# LoRa_Gateway_ESP32_-_Final.net
KiCad netlist of a schematic drawn in EAGLE
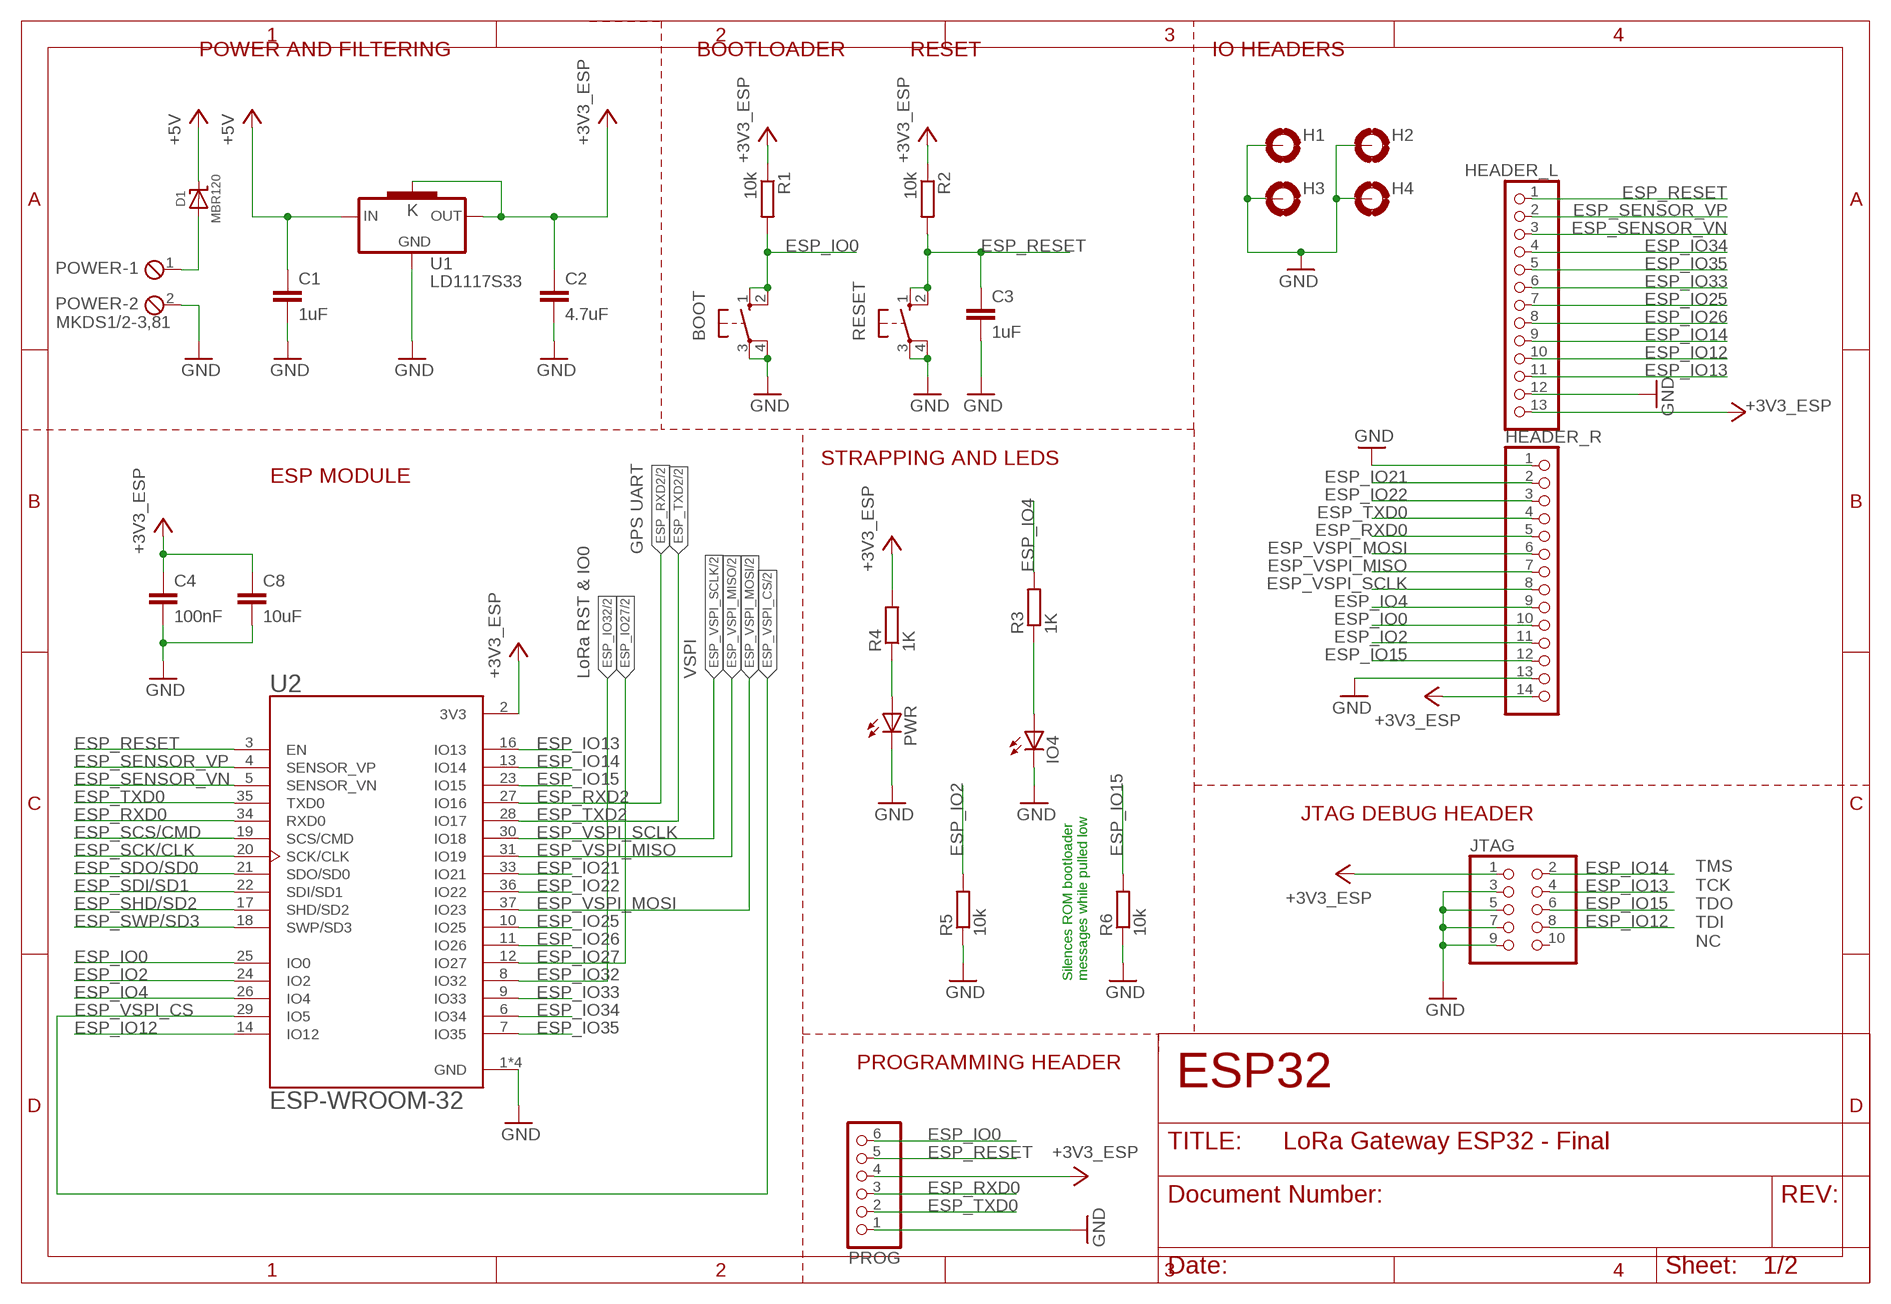
[diagram p0: schematic, sheet 1]
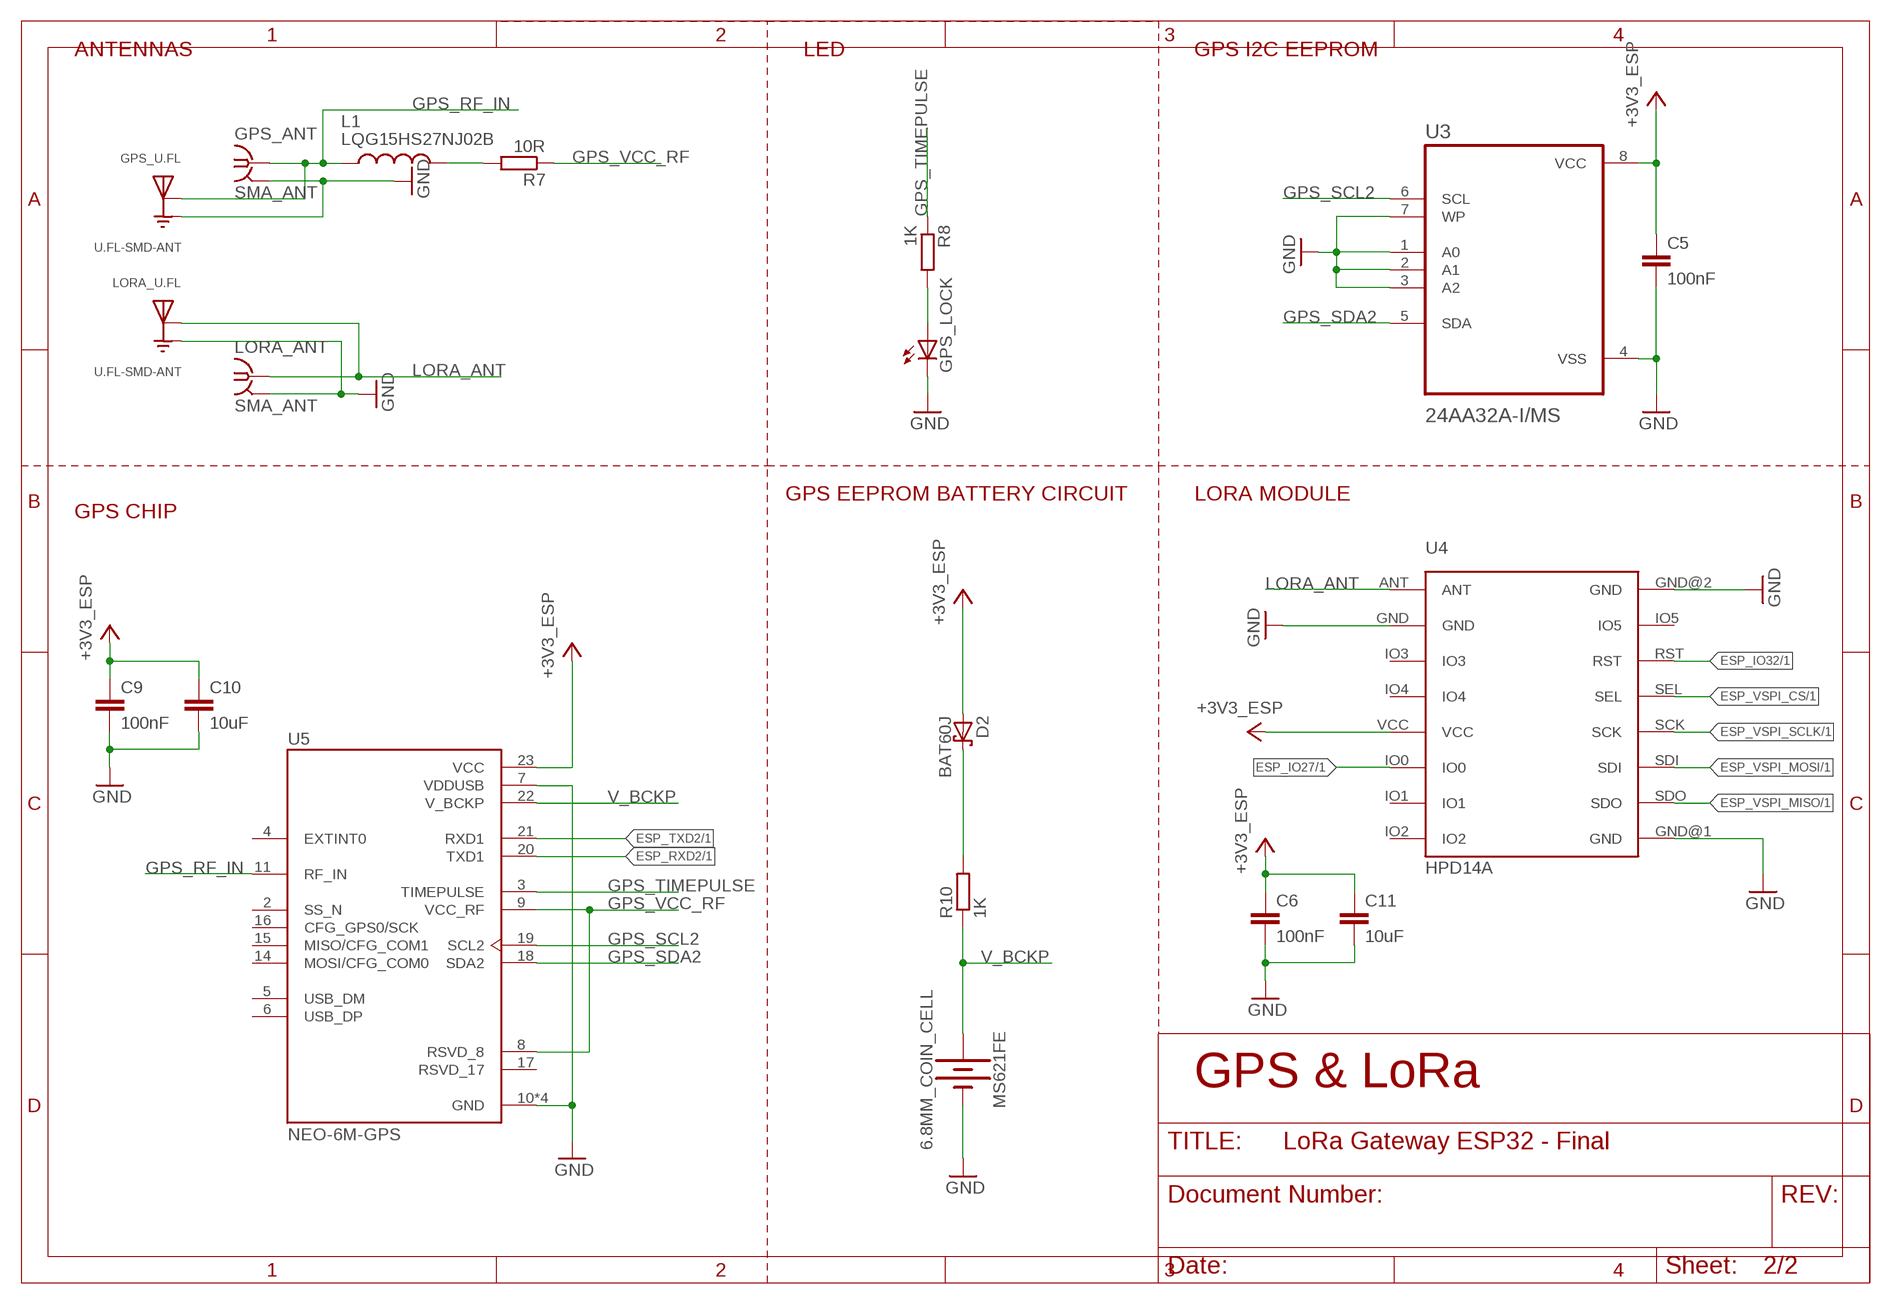
[diagram p1: schematic, sheet 2]

(export (version "E")
  (design (tool "Eeschema 10.0.6"))
  (components
    (comp (ref "C5")
      (value "100nF")
      (footprint "eagle-import:C0805K")
      (libsource (lib "eagle-import") (part "C-EUC0805K"))
    )
    (comp (ref "C6")
      (value "100nF")
      (footprint "eagle-import:C0805K")
      (libsource (lib "eagle-import") (part "C-EUC0805K"))
    )
    (comp (ref "C9")
      (value "100nF")
      (footprint "eagle-import:C0805K")
      (libsource (lib "eagle-import") (part "C-EUC0805K"))
    )
    (comp (ref "C10")
      (value "10uF")
      (footprint "eagle-import:C0805K")
      (libsource (lib "eagle-import") (part "C-EUC0805K"))
    )
    (comp (ref "C11")
      (value "10uF")
      (footprint "eagle-import:C0805K")
      (libsource (lib "eagle-import") (part "C-EUC0805K"))
    )
    (comp (ref "D2")
      (value "BAT60J")
      (footprint "eagle-import:SOD323_ST")
      (libsource (lib "eagle-import") (part "BAT60J"))
    )
    (comp (ref "GPS_ANT")
      (value "SMA_ANT")
      (footprint "eagle-import:BU-SMA-H")
      (libsource (lib "eagle-import") (part "SMA_ANT"))
    )
    (comp (ref "GPS_LOCK")
      (value "LEDCHIP-LED0805")
      (footprint "eagle-import:CHIP-LED0805")
      (libsource (lib "eagle-import") (part "LEDCHIP-LED0805"))
    )
    (comp (ref "GPS_U.FL")
      (value "U.FL-SMD-ANT")
      (footprint "eagle-import:HRS_U.FL-R-SMT-1(10)")
      (fields (field (name "MF") "Hirose") (field (name "MP") "U.FL-R-SMT-1(10)"))
      (libsource (lib "eagle-import") (part "U.FL-SMD-ANT"))
    )
    (comp (ref "L1")
      (value "LQG15HS27NJ02B")
      (footprint "eagle-import:INDC1005X55N")
      (fields (field (name "MF") "Murata"))
      (libsource (lib "eagle-import") (part "LQG15HS27NJ02B"))
    )
    (comp (ref "LORA_ANT")
      (value "SMA_ANT")
      (footprint "eagle-import:BU-SMA-H")
      (libsource (lib "eagle-import") (part "SMA_ANT"))
    )
    (comp (ref "LORA_U.FL")
      (value "U.FL-SMD-ANT")
      (footprint "eagle-import:HRS_U.FL-R-SMT-1(10)")
      (fields (field (name "MF") "Hirose") (field (name "MP") "U.FL-R-SMT-1(10)"))
      (libsource (lib "eagle-import") (part "U.FL-SMD-ANT"))
    )
    (comp (ref "MS621FE")
      (value "6.8MM_COIN_CELL")
      (footprint "eagle-import:BATTCON-6.8MM")
      (libsource (lib "eagle-import") (part "BATTERY-6.8MM_SMD"))
    )
    (comp (ref "R7")
      (value "10R")
      (footprint "eagle-import:R0805")
      (libsource (lib "eagle-import") (part "R-EU_R0805"))
    )
    (comp (ref "R8")
      (value "1K")
      (footprint "eagle-import:R0805")
      (libsource (lib "eagle-import") (part "R-EU_R0805"))
    )
    (comp (ref "R10")
      (value "1K")
      (footprint "eagle-import:R0805")
      (libsource (lib "eagle-import") (part "R-EU_R0805"))
    )
    (comp (ref "U3")
      (value "24AA32A-I/MS")
      (footprint "eagle-import:SOP65P490X110-8N")
      (fields (field (name "MF") "Microchip"))
      (libsource (lib "eagle-import") (part "24AA32A-I/MS"))
    )
    (comp (ref "U4")
      (value "HPD14A")
      (footprint "eagle-import:HPD14A")
      (libsource (lib "eagle-import") (part "HPD14A"))
    )
    (comp (ref "U5")
      (value "NEO-6M-GPS")
      (footprint "eagle-import:XCVR_NEO-6M-GPS")
      (fields (field (name "MF") "u-blox"))
      (libsource (lib "eagle-import") (part "NEO-6M-GPS"))
    )
    (comp (ref "BOOT")
      (value "10-XX")
      (footprint "eagle-import:B3F-10XX")
      (fields (field (name "MPN") "B3F-1000"))
      (libsource (lib "eagle-import") (part "10-XX"))
    )
    (comp (ref "C1")
      (value "1uF")
      (footprint "eagle-import:C0805K")
      (libsource (lib "eagle-import") (part "C-EUC0805K"))
    )
    (comp (ref "C2")
      (value "4.7uF")
      (footprint "eagle-import:C0805K")
      (libsource (lib "eagle-import") (part "C-EUC0805K"))
    )
    (comp (ref "C3")
      (value "1uF")
      (footprint "eagle-import:C0805K")
      (libsource (lib "eagle-import") (part "C-EUC0805K"))
    )
    (comp (ref "C4")
      (value "100nF")
      (footprint "eagle-import:C0805K")
      (libsource (lib "eagle-import") (part "C-EUC0805K"))
    )
    (comp (ref "C8")
      (value "10uF")
      (footprint "eagle-import:C0805K")
      (libsource (lib "eagle-import") (part "C-EUC0805K"))
    )
    (comp (ref "D1")
      (value "MBR120")
      (footprint "eagle-import:SOD-123")
      (libsource (lib "eagle-import") (part "DIODE-SCHOTTKYSOD-123"))
    )
    (comp (ref "H1")
      (value "MOUNT-PAD-ROUND3.2")
      (footprint "eagle-import:3,2-PAD")
      (libsource (lib "eagle-import") (part "MOUNT-PAD-ROUND3.2"))
    )
    (comp (ref "H2")
      (value "MOUNT-PAD-ROUND3.2")
      (footprint "eagle-import:3,2-PAD")
      (libsource (lib "eagle-import") (part "MOUNT-PAD-ROUND3.2"))
    )
    (comp (ref "H3")
      (value "MOUNT-PAD-ROUND3.2")
      (footprint "eagle-import:3,2-PAD")
      (libsource (lib "eagle-import") (part "MOUNT-PAD-ROUND3.2"))
    )
    (comp (ref "H4")
      (value "MOUNT-PAD-ROUND3.2")
      (footprint "eagle-import:3,2-PAD")
      (libsource (lib "eagle-import") (part "MOUNT-PAD-ROUND3.2"))
    )
    (comp (ref "HEADER_L")
      (value "PINHD-1X13")
      (footprint "eagle-import:1X13")
      (libsource (lib "eagle-import") (part "PINHD-1X13"))
    )
    (comp (ref "HEADER_R")
      (value "PINHD-1X14")
      (footprint "eagle-import:1X14")
      (libsource (lib "eagle-import") (part "PINHD-1X14"))
    )
    (comp (ref "IO4")
      (value "LEDCHIP-LED0805")
      (footprint "eagle-import:CHIP-LED0805")
      (libsource (lib "eagle-import") (part "LEDCHIP-LED0805"))
    )
    (comp (ref "JTAG")
      (value "PINHD-2X5")
      (footprint "eagle-import:2X05")
      (libsource (lib "eagle-import") (part "PINHD-2X5"))
    )
    (comp (ref "POWER")
      (value "MKDS1/2-3,81")
      (footprint "eagle-import:2POL381")
      (libsource (lib "eagle-import") (part "MKDS1/2-3,81"))
    )
    (comp (ref "PROG")
      (value "PINHD-1X6")
      (footprint "eagle-import:1X06")
      (libsource (lib "eagle-import") (part "PINHD-1X6"))
    )
    (comp (ref "PWR")
      (value "LEDCHIP-LED0805")
      (footprint "eagle-import:CHIP-LED0805")
      (libsource (lib "eagle-import") (part "LEDCHIP-LED0805"))
    )
    (comp (ref "R1")
      (value "10k")
      (footprint "eagle-import:R0805")
      (libsource (lib "eagle-import") (part "R-EU_R0805"))
    )
    (comp (ref "R2")
      (value "10k")
      (footprint "eagle-import:R0805")
      (libsource (lib "eagle-import") (part "R-EU_R0805"))
    )
    (comp (ref "R3")
      (value "1K")
      (footprint "eagle-import:R0805")
      (libsource (lib "eagle-import") (part "R-EU_R0805"))
    )
    (comp (ref "R4")
      (value "1K")
      (footprint "eagle-import:R0805")
      (libsource (lib "eagle-import") (part "R-EU_R0805"))
    )
    (comp (ref "R5")
      (value "10k")
      (footprint "eagle-import:R0805")
      (libsource (lib "eagle-import") (part "R-EU_R0805"))
    )
    (comp (ref "R6")
      (value "10k")
      (footprint "eagle-import:R0805")
      (libsource (lib "eagle-import") (part "R-EU_R0805"))
    )
    (comp (ref "RESET")
      (value "10-XX")
      (footprint "eagle-import:B3F-10XX")
      (fields (field (name "MPN") "B3F-1000"))
      (libsource (lib "eagle-import") (part "10-XX"))
    )
    (comp (ref "U1")
      (value "LD1117S33")
      (footprint "eagle-import:SOT223")
      (fields (field (name "MF") "STMicroelectronics"))
      (libsource (lib "eagle-import") (part "LD1117S33"))
    )
    (comp (ref "U2")
      (value "ESP-WROOM-32")
      (footprint "eagle-import:MODULE_ESP-WROOM-32")
      (fields (field (name "MF") "Olimex LTD"))
      (libsource (lib "eagle-import") (part "ESP-WROOM-32"))
    )
  )
  (nets
    (net (code "1") (name "+3V3_ESP") (class "Default")
      (node (ref "C10") (pin "1") (pinfunction "1_1") (pintype "passive"))
      (node (ref "C11") (pin "1") (pinfunction "1_1") (pintype "passive"))
      (node (ref "C2") (pin "1") (pinfunction "1_1") (pintype "passive"))
      (node (ref "C4") (pin "1") (pinfunction "1_1") (pintype "passive"))
      (node (ref "C5") (pin "1") (pinfunction "1_1") (pintype "passive"))
      (node (ref "C6") (pin "1") (pinfunction "1_1") (pintype "passive"))
      (node (ref "C8") (pin "1") (pinfunction "1_1") (pintype "passive"))
      (node (ref "C9") (pin "1") (pinfunction "1_1") (pintype "passive"))
      (node (ref "D2") (pin "A") (pinfunction "A_A") (pintype "passive"))
      (node (ref "HEADER_L") (pin "13") (pinfunction "13_13") (pintype "passive"))
      (node (ref "HEADER_R") (pin "14") (pinfunction "14_14") (pintype "passive"))
      (node (ref "JTAG") (pin "1") (pinfunction "1_1") (pintype "passive"))
      (node (ref "PROG") (pin "4") (pinfunction "4_4") (pintype "passive"))
      (node (ref "R1") (pin "1") (pinfunction "1_1") (pintype "passive"))
      (node (ref "R2") (pin "1") (pinfunction "1_1") (pintype "passive"))
      (node (ref "R4") (pin "2") (pinfunction "2_2") (pintype "passive"))
      (node (ref "U1") (pin "2") (pinfunction "OUT_2") (pintype "passive"))
      (node (ref "U1") (pin "4") (pinfunction "K_4") (pintype "passive"))
      (node (ref "U2") (pin "2") (pinfunction "3V3_2") (pintype "power_in"))
      (node (ref "U3") (pin "8") (pinfunction "VCC_8") (pintype "power_in"))
      (node (ref "U4") (pin "VCC") (pinfunction "VCC_VCC") (pintype "bidirectional"))
      (node (ref "U5") (pin "23") (pinfunction "VCC_23") (pintype "power_in"))
    )
    (net (code "2") (name "+5V") (class "Default")
      (node (ref "C1") (pin "1") (pinfunction "1_1") (pintype "passive"))
      (node (ref "D1") (pin "C") (pinfunction "C_C") (pintype "passive"))
      (node (ref "U1") (pin "3") (pinfunction "IN_3") (pintype "input"))
    )
    (net (code "3") (name "ESP_IO0") (class "Default")
      (node (ref "BOOT") (pin "1") (pinfunction "S_1") (pintype "passive"))
      (node (ref "BOOT") (pin "2") (pinfunction "S1_2") (pintype "passive"))
      (node (ref "HEADER_R") (pin "10") (pinfunction "10_10") (pintype "passive"))
      (node (ref "PROG") (pin "6") (pinfunction "6_6") (pintype "passive"))
      (node (ref "R1") (pin "2") (pinfunction "2_2") (pintype "passive"))
      (node (ref "U2") (pin "25") (pinfunction "IO0_25") (pintype "bidirectional"))
    )
    (net (code "4") (name "ESP_IO2") (class "Default")
      (node (ref "HEADER_R") (pin "11") (pinfunction "11_11") (pintype "passive"))
      (node (ref "R5") (pin "2") (pinfunction "2_2") (pintype "passive"))
      (node (ref "U2") (pin "24") (pinfunction "IO2_24") (pintype "bidirectional"))
    )
    (net (code "5") (name "ESP_IO4") (class "Default")
      (node (ref "HEADER_R") (pin "9") (pinfunction "9_9") (pintype "passive"))
      (node (ref "R3") (pin "2") (pinfunction "2_2") (pintype "passive"))
      (node (ref "U2") (pin "26") (pinfunction "IO4_26") (pintype "bidirectional"))
    )
    (net (code "6") (name "ESP_IO12") (class "Default")
      (node (ref "HEADER_L") (pin "10") (pinfunction "10_10") (pintype "passive"))
      (node (ref "JTAG") (pin "8") (pinfunction "8_8") (pintype "passive"))
      (node (ref "U2") (pin "14") (pinfunction "IO12_14") (pintype "bidirectional"))
    )
    (net (code "7") (name "ESP_IO13") (class "Default")
      (node (ref "HEADER_L") (pin "11") (pinfunction "11_11") (pintype "passive"))
      (node (ref "JTAG") (pin "4") (pinfunction "4_4") (pintype "passive"))
      (node (ref "U2") (pin "16") (pinfunction "IO13_16") (pintype "bidirectional"))
    )
    (net (code "8") (name "ESP_IO14") (class "Default")
      (node (ref "HEADER_L") (pin "9") (pinfunction "9_9") (pintype "passive"))
      (node (ref "JTAG") (pin "2") (pinfunction "2_2") (pintype "passive"))
      (node (ref "U2") (pin "13") (pinfunction "IO14_13") (pintype "bidirectional"))
    )
    (net (code "9") (name "ESP_IO15") (class "Default")
      (node (ref "HEADER_R") (pin "12") (pinfunction "12_12") (pintype "passive"))
      (node (ref "JTAG") (pin "6") (pinfunction "6_6") (pintype "passive"))
      (node (ref "R6") (pin "2") (pinfunction "2_2") (pintype "passive"))
      (node (ref "U2") (pin "23") (pinfunction "IO15_23") (pintype "bidirectional"))
    )
    (net (code "10") (name "ESP_IO21") (class "Default")
      (node (ref "HEADER_R") (pin "2") (pinfunction "2_2") (pintype "passive"))
      (node (ref "U2") (pin "33") (pinfunction "IO21_33") (pintype "bidirectional"))
    )
    (net (code "11") (name "ESP_IO22") (class "Default")
      (node (ref "HEADER_R") (pin "3") (pinfunction "3_3") (pintype "passive"))
      (node (ref "U2") (pin "36") (pinfunction "IO22_36") (pintype "bidirectional"))
    )
    (net (code "12") (name "ESP_IO25") (class "Default")
      (node (ref "HEADER_L") (pin "7") (pinfunction "7_7") (pintype "passive"))
      (node (ref "U2") (pin "10") (pinfunction "IO25_10") (pintype "bidirectional"))
    )
    (net (code "13") (name "ESP_IO26") (class "Default")
      (node (ref "HEADER_L") (pin "8") (pinfunction "8_8") (pintype "passive"))
      (node (ref "U2") (pin "11") (pinfunction "IO26_11") (pintype "bidirectional"))
    )
    (net (code "14") (name "ESP_IO27") (class "Default")
      (node (ref "U2") (pin "12") (pinfunction "IO27_12") (pintype "bidirectional"))
      (node (ref "U4") (pin "IO0") (pinfunction "IO0_IO0") (pintype "bidirectional"))
    )
    (net (code "15") (name "ESP_IO32") (class "Default")
      (node (ref "U2") (pin "8") (pinfunction "IO32_8") (pintype "bidirectional"))
      (node (ref "U4") (pin "RST") (pinfunction "RST_RST") (pintype "bidirectional"))
    )
    (net (code "16") (name "ESP_IO33") (class "Default")
      (node (ref "HEADER_L") (pin "6") (pinfunction "6_6") (pintype "passive"))
      (node (ref "U2") (pin "9") (pinfunction "IO33_9") (pintype "bidirectional"))
    )
    (net (code "17") (name "ESP_IO34") (class "Default")
      (node (ref "HEADER_L") (pin "4") (pinfunction "4_4") (pintype "passive"))
      (node (ref "U2") (pin "6") (pinfunction "IO34_6") (pintype "bidirectional"))
    )
    (net (code "18") (name "ESP_IO35") (class "Default")
      (node (ref "HEADER_L") (pin "5") (pinfunction "5_5") (pintype "passive"))
      (node (ref "U2") (pin "7") (pinfunction "IO35_7") (pintype "bidirectional"))
    )
    (net (code "19") (name "ESP_RESET") (class "Default")
      (node (ref "C3") (pin "1") (pinfunction "1_1") (pintype "passive"))
      (node (ref "HEADER_L") (pin "1") (pinfunction "1_1") (pintype "passive"))
      (node (ref "PROG") (pin "5") (pinfunction "5_5") (pintype "passive"))
      (node (ref "R2") (pin "2") (pinfunction "2_2") (pintype "passive"))
      (node (ref "RESET") (pin "1") (pinfunction "S_1") (pintype "passive"))
      (node (ref "RESET") (pin "2") (pinfunction "S1_2") (pintype "passive"))
      (node (ref "U2") (pin "3") (pinfunction "EN_3") (pintype "input"))
    )
    (net (code "20") (name "ESP_RXD0") (class "Default")
      (node (ref "HEADER_R") (pin "5") (pinfunction "5_5") (pintype "passive"))
      (node (ref "PROG") (pin "3") (pinfunction "3_3") (pintype "passive"))
      (node (ref "U2") (pin "34") (pinfunction "RXD0_34") (pintype "bidirectional"))
    )
    (net (code "21") (name "ESP_RXD2") (class "Default")
      (node (ref "U2") (pin "27") (pinfunction "IO16_27") (pintype "bidirectional"))
      (node (ref "U5") (pin "20") (pinfunction "TXD1_20") (pintype "output"))
    )
    (net (code "22") (name "ESP_SCK{slash}CLK") (class "Default")
      (node (ref "U2") (pin "20") (pinfunction "SCK/CLK_20") (pintype "bidirectional"))
    )
    (net (code "23") (name "ESP_SCS{slash}CMD") (class "Default")
      (node (ref "U2") (pin "19") (pinfunction "SCS/CMD_19") (pintype "bidirectional"))
    )
    (net (code "24") (name "ESP_SDI{slash}SD1") (class "Default")
      (node (ref "U2") (pin "22") (pinfunction "SDI/SD1_22") (pintype "bidirectional"))
    )
    (net (code "25") (name "ESP_SDO{slash}SD0") (class "Default")
      (node (ref "U2") (pin "21") (pinfunction "SDO/SD0_21") (pintype "bidirectional"))
    )
    (net (code "26") (name "ESP_SENSOR_VN") (class "Default")
      (node (ref "HEADER_L") (pin "3") (pinfunction "3_3") (pintype "passive"))
      (node (ref "U2") (pin "5") (pinfunction "SENSOR_VN_5") (pintype "input"))
    )
    (net (code "27") (name "ESP_SENSOR_VP") (class "Default")
      (node (ref "HEADER_L") (pin "2") (pinfunction "2_2") (pintype "passive"))
      (node (ref "U2") (pin "4") (pinfunction "SENSOR_VP_4") (pintype "input"))
    )
    (net (code "28") (name "ESP_SHD{slash}SD2") (class "Default")
      (node (ref "U2") (pin "17") (pinfunction "SHD/SD2_17") (pintype "bidirectional"))
    )
    (net (code "29") (name "ESP_SWP{slash}SD3") (class "Default")
      (node (ref "U2") (pin "18") (pinfunction "SWP/SD3_18") (pintype "bidirectional"))
    )
    (net (code "30") (name "ESP_TXD0") (class "Default")
      (node (ref "HEADER_R") (pin "4") (pinfunction "4_4") (pintype "passive"))
      (node (ref "PROG") (pin "2") (pinfunction "2_2") (pintype "passive"))
      (node (ref "U2") (pin "35") (pinfunction "TXD0_35") (pintype "bidirectional"))
    )
    (net (code "31") (name "ESP_TXD2") (class "Default")
      (node (ref "U2") (pin "28") (pinfunction "IO17_28") (pintype "bidirectional"))
      (node (ref "U5") (pin "21") (pinfunction "RXD1_21") (pintype "input"))
    )
    (net (code "32") (name "ESP_VSPI_CS") (class "Default")
      (node (ref "U2") (pin "29") (pinfunction "IO5_29") (pintype "bidirectional"))
      (node (ref "U4") (pin "SEL") (pinfunction "SEL_SEL") (pintype "bidirectional"))
    )
    (net (code "33") (name "ESP_VSPI_MISO") (class "Default")
      (node (ref "HEADER_R") (pin "7") (pinfunction "7_7") (pintype "passive"))
      (node (ref "U2") (pin "31") (pinfunction "IO19_31") (pintype "bidirectional"))
      (node (ref "U4") (pin "SDO") (pinfunction "SDO_SDO") (pintype "bidirectional"))
    )
    (net (code "34") (name "ESP_VSPI_MOSI") (class "Default")
      (node (ref "HEADER_R") (pin "6") (pinfunction "6_6") (pintype "passive"))
      (node (ref "U2") (pin "37") (pinfunction "IO23_37") (pintype "bidirectional"))
      (node (ref "U4") (pin "SDI") (pinfunction "SDI_SDI") (pintype "bidirectional"))
    )
    (net (code "35") (name "ESP_VSPI_SCLK") (class "Default")
      (node (ref "HEADER_R") (pin "8") (pinfunction "8_8") (pintype "passive"))
      (node (ref "U2") (pin "30") (pinfunction "IO18_30") (pintype "bidirectional"))
      (node (ref "U4") (pin "SCK") (pinfunction "SCK_SCK") (pintype "bidirectional"))
    )
    (net (code "36") (name "GND") (class "Default")
      (node (ref "BOOT") (pin "3") (pinfunction "P_3") (pintype "passive"))
      (node (ref "BOOT") (pin "4") (pinfunction "P1_4") (pintype "passive"))
      (node (ref "C1") (pin "2") (pinfunction "2_2") (pintype "passive"))
      (node (ref "C10") (pin "2") (pinfunction "2_2") (pintype "passive"))
      (node (ref "C11") (pin "2") (pinfunction "2_2") (pintype "passive"))
      (node (ref "C2") (pin "2") (pinfunction "2_2") (pintype "passive"))
      (node (ref "C3") (pin "2") (pinfunction "2_2") (pintype "passive"))
      (node (ref "C4") (pin "2") (pinfunction "2_2") (pintype "passive"))
      (node (ref "C5") (pin "2") (pinfunction "2_2") (pintype "passive"))
      (node (ref "C6") (pin "2") (pinfunction "2_2") (pintype "passive"))
      (node (ref "C8") (pin "2") (pinfunction "2_2") (pintype "passive"))
      (node (ref "C9") (pin "2") (pinfunction "2_2") (pintype "passive"))
      (node (ref "GPS_ANT") (pin "2") (pinfunction "2_2") (pintype "passive"))
      (node (ref "GPS_ANT") (pin "3") (pinfunction "2_3") (pintype "passive"))
      (node (ref "GPS_ANT") (pin "4") (pinfunction "2_4") (pintype "passive"))
      (node (ref "GPS_ANT") (pin "5") (pinfunction "2_5") (pintype "passive"))
      (node (ref "GPS_LOCK") (pin "C") (pinfunction "C_C") (pintype "passive"))
      (node (ref "GPS_U.FL") (pin "1") (pinfunction "GND_1") (pintype "passive"))
      (node (ref "GPS_U.FL") (pin "3") (pinfunction "GND_3") (pintype "passive"))
      (node (ref "H1") (pin "B3,2") (pinfunction "MOUNT_B3,2") (pintype "passive"))
      (node (ref "H2") (pin "B3,2") (pinfunction "MOUNT_B3,2") (pintype "passive"))
      (node (ref "H3") (pin "B3,2") (pinfunction "MOUNT_B3,2") (pintype "passive"))
      (node (ref "H4") (pin "B3,2") (pinfunction "MOUNT_B3,2") (pintype "passive"))
      (node (ref "HEADER_L") (pin "12") (pinfunction "12_12") (pintype "passive"))
      (node (ref "HEADER_R") (pin "1") (pinfunction "1_1") (pintype "passive"))
      (node (ref "HEADER_R") (pin "13") (pinfunction "13_13") (pintype "passive"))
      (node (ref "IO4") (pin "C") (pinfunction "C_C") (pintype "passive"))
      (node (ref "JTAG") (pin "3") (pinfunction "3_3") (pintype "passive"))
      (node (ref "JTAG") (pin "5") (pinfunction "5_5") (pintype "passive"))
      (node (ref "JTAG") (pin "7") (pinfunction "7_7") (pintype "passive"))
      (node (ref "JTAG") (pin "9") (pinfunction "9_9") (pintype "passive"))
      (node (ref "LORA_ANT") (pin "2") (pinfunction "2_2") (pintype "passive"))
      (node (ref "LORA_ANT") (pin "3") (pinfunction "2_3") (pintype "passive"))
      (node (ref "LORA_ANT") (pin "4") (pinfunction "2_4") (pintype "passive"))
      (node (ref "LORA_ANT") (pin "5") (pinfunction "2_5") (pintype "passive"))
      (node (ref "LORA_U.FL") (pin "1") (pinfunction "GND_1") (pintype "passive"))
      (node (ref "LORA_U.FL") (pin "3") (pinfunction "GND_3") (pintype "passive"))
      (node (ref "MS621FE") (pin "-") (pinfunction "-_-") (pintype "power_in"))
      (node (ref "POWER") (pin "2") (pinfunction "1_2") (pintype "passive"))
      (node (ref "PROG") (pin "1") (pinfunction "1_1") (pintype "passive"))
      (node (ref "PWR") (pin "C") (pinfunction "C_C") (pintype "passive"))
      (node (ref "R5") (pin "1") (pinfunction "1_1") (pintype "passive"))
      (node (ref "R6") (pin "1") (pinfunction "1_1") (pintype "passive"))
      (node (ref "RESET") (pin "3") (pinfunction "P_3") (pintype "passive"))
      (node (ref "RESET") (pin "4") (pinfunction "P1_4") (pintype "passive"))
      (node (ref "U1") (pin "1") (pinfunction "GND_1") (pintype "input"))
      (node (ref "U2") (pin "1") (pinfunction "GND_1") (pintype "power_in"))
      (node (ref "U2") (pin "1.1") (pinfunction "GND_1.1") (pintype "power_in"))
      (node (ref "U2") (pin "15") (pinfunction "GND_15") (pintype "power_in"))
      (node (ref "U2") (pin "38") (pinfunction "GND_38") (pintype "power_in"))
      (node (ref "U3") (pin "1") (pinfunction "A0_1") (pintype "bidirectional"))
      (node (ref "U3") (pin "2") (pinfunction "A1_2") (pintype "bidirectional"))
      (node (ref "U3") (pin "3") (pinfunction "A2_3") (pintype "bidirectional"))
      (node (ref "U3") (pin "4") (pinfunction "VSS_4") (pintype "power_in"))
      (node (ref "U3") (pin "7") (pinfunction "WP_7") (pintype "input"))
      (node (ref "U4") (pin "GND") (pinfunction "GND_GND") (pintype "bidirectional"))
      (node (ref "U4") (pin "GND@1") (pinfunction "GND_GND@1") (pintype "bidirectional"))
      (node (ref "U4") (pin "GND@2") (pinfunction "GND_GND@2") (pintype "bidirectional"))
      (node (ref "U5") (pin "10") (pinfunction "GND_10") (pintype "power_in"))
      (node (ref "U5") (pin "12") (pinfunction "GND_12") (pintype "power_in"))
      (node (ref "U5") (pin "13") (pinfunction "GND_13") (pintype "power_in"))
      (node (ref "U5") (pin "24") (pinfunction "GND_24") (pintype "power_in"))
      (node (ref "U5") (pin "7") (pinfunction "VDDUSB_7") (pintype "power_in"))
    )
    (net (code "37") (name "GPS_RF_IN") (class "Default")
      (node (ref "GPS_ANT") (pin "1") (pinfunction "1_1") (pintype "passive"))
      (node (ref "GPS_U.FL") (pin "2") (pinfunction "SIG_2") (pintype "passive"))
      (node (ref "L1") (pin "1") (pinfunction "1_1") (pintype "passive"))
      (node (ref "U5") (pin "11") (pinfunction "RF_IN_11") (pintype "input"))
    )
    (net (code "38") (name "GPS_SCL2") (class "Default")
      (node (ref "U3") (pin "6") (pinfunction "SCL_6") (pintype "input"))
      (node (ref "U5") (pin "19") (pinfunction "SCL2_19") (pintype "bidirectional"))
    )
    (net (code "39") (name "GPS_SDA2") (class "Default")
      (node (ref "U3") (pin "5") (pinfunction "SDA_5") (pintype "bidirectional"))
      (node (ref "U5") (pin "18") (pinfunction "SDA2_18") (pintype "bidirectional"))
    )
    (net (code "40") (name "GPS_TIMEPULSE") (class "Default")
      (node (ref "R8") (pin "1") (pinfunction "1_1") (pintype "passive"))
      (node (ref "U5") (pin "3") (pinfunction "TIMEPULSE_3") (pintype "output"))
    )
    (net (code "41") (name "GPS_VCC_RF") (class "Default")
      (node (ref "R7") (pin "1") (pinfunction "1_1") (pintype "passive"))
      (node (ref "U5") (pin "8") (pinfunction "RSVD_8_8") (pintype "passive"))
      (node (ref "U5") (pin "9") (pinfunction "VCC_RF_9") (pintype "output"))
    )
    (net (code "42") (name "LORA_ANT") (class "Default")
      (node (ref "LORA_ANT") (pin "1") (pinfunction "1_1") (pintype "passive"))
      (node (ref "LORA_U.FL") (pin "2") (pinfunction "SIG_2") (pintype "passive"))
      (node (ref "U4") (pin "ANT") (pinfunction "ANT_ANT") (pintype "bidirectional"))
    )
    (net (code "43") (name "Net-(D1-PadA)") (class "Default")
      (node (ref "D1") (pin "A") (pinfunction "A_A") (pintype "passive"))
      (node (ref "POWER") (pin "1") (pinfunction "1_1") (pintype "passive"))
    )
    (net (code "44") (name "Net-(D2-PadC)") (class "Default")
      (node (ref "D2") (pin "C") (pinfunction "C_C") (pintype "passive"))
      (node (ref "R10") (pin "2") (pinfunction "2_2") (pintype "passive"))
    )
    (net (code "45") (name "Net-(GPS_LOCK-PadA)") (class "Default")
      (node (ref "GPS_LOCK") (pin "A") (pinfunction "A_A") (pintype "passive"))
      (node (ref "R8") (pin "2") (pinfunction "2_2") (pintype "passive"))
    )
    (net (code "46") (name "Net-(IO4-PadA)") (class "Default")
      (node (ref "IO4") (pin "A") (pinfunction "A_A") (pintype "passive"))
      (node (ref "R3") (pin "1") (pinfunction "1_1") (pintype "passive"))
    )
    (net (code "47") (name "Net-(L1-Pad2)") (class "Default")
      (node (ref "L1") (pin "2") (pinfunction "2_2") (pintype "passive"))
      (node (ref "R7") (pin "2") (pinfunction "2_2") (pintype "passive"))
    )
    (net (code "48") (name "Net-(PWR-PadA)") (class "Default")
      (node (ref "PWR") (pin "A") (pinfunction "A_A") (pintype "passive"))
      (node (ref "R4") (pin "1") (pinfunction "1_1") (pintype "passive"))
    )
    (net (code "49") (name "V_BCKP") (class "Default")
      (node (ref "MS621FE") (pin "+") (pinfunction "+_+") (pintype "power_in"))
      (node (ref "R10") (pin "1") (pinfunction "1_1") (pintype "passive"))
      (node (ref "U5") (pin "22") (pinfunction "V_BCKP_22") (pintype "power_in"))
    )
    (net (code "50") (name "unconnected-(JTAG-Pad10)") (class "Default")
      (node (ref "JTAG") (pin "10") (pinfunction "10_10") (pintype "passive"))
    )
    (net (code "51") (name "unconnected-(U4-PadIO1)") (class "Default")
      (node (ref "U4") (pin "IO1") (pinfunction "IO1_IO1") (pintype "bidirectional"))
    )
    (net (code "52") (name "unconnected-(U4-PadIO2)") (class "Default")
      (node (ref "U4") (pin "IO2") (pinfunction "IO2_IO2") (pintype "bidirectional"))
    )
    (net (code "53") (name "unconnected-(U4-PadIO3)") (class "Default")
      (node (ref "U4") (pin "IO3") (pinfunction "IO3_IO3") (pintype "bidirectional"))
    )
    (net (code "54") (name "unconnected-(U4-PadIO4)") (class "Default")
      (node (ref "U4") (pin "IO4") (pinfunction "IO4_IO4") (pintype "bidirectional"))
    )
    (net (code "55") (name "unconnected-(U4-PadIO5)") (class "Default")
      (node (ref "U4") (pin "IO5") (pinfunction "IO5_IO5") (pintype "bidirectional"))
    )
    (net (code "56") (name "unconnected-(U5-CFG_GPS0{slash}SCK-Pad16)") (class "Default")
      (node (ref "U5") (pin "16") (pinfunction "CFG_GPS0/SCK_16") (pintype "input"))
    )
    (net (code "57") (name "unconnected-(U5-EXTINT0-Pad4)") (class "Default")
      (node (ref "U5") (pin "4") (pinfunction "EXTINT0_4") (pintype "input"))
    )
    (net (code "58") (name "unconnected-(U5-MISO{slash}CFG_COM1-Pad15)") (class "Default")
      (node (ref "U5") (pin "15") (pinfunction "MISO/CFG_COM1_15") (pintype "input"))
    )
    (net (code "59") (name "unconnected-(U5-MOSI{slash}CFG_COM0-Pad14)") (class "Default")
      (node (ref "U5") (pin "14") (pinfunction "MOSI/CFG_COM0_14") (pintype "bidirectional"))
    )
    (net (code "60") (name "unconnected-(U5-RSVD_17-Pad17)") (class "Default")
      (node (ref "U5") (pin "17") (pinfunction "RSVD_17_17") (pintype "passive"))
    )
    (net (code "61") (name "unconnected-(U5-SS_N-Pad2)") (class "Default")
      (node (ref "U5") (pin "2") (pinfunction "SS_N_2") (pintype "input"))
    )
    (net (code "62") (name "unconnected-(U5-USB_DM-Pad5)") (class "Default")
      (node (ref "U5") (pin "5") (pinfunction "USB_DM_5") (pintype "bidirectional"))
    )
    (net (code "63") (name "unconnected-(U5-USB_DP-Pad6)") (class "Default")
      (node (ref "U5") (pin "6") (pinfunction "USB_DP_6") (pintype "bidirectional"))
    )
  )
)
